# Battery_Charger.net
KiCad netlist of a schematic drawn in Altium Designer
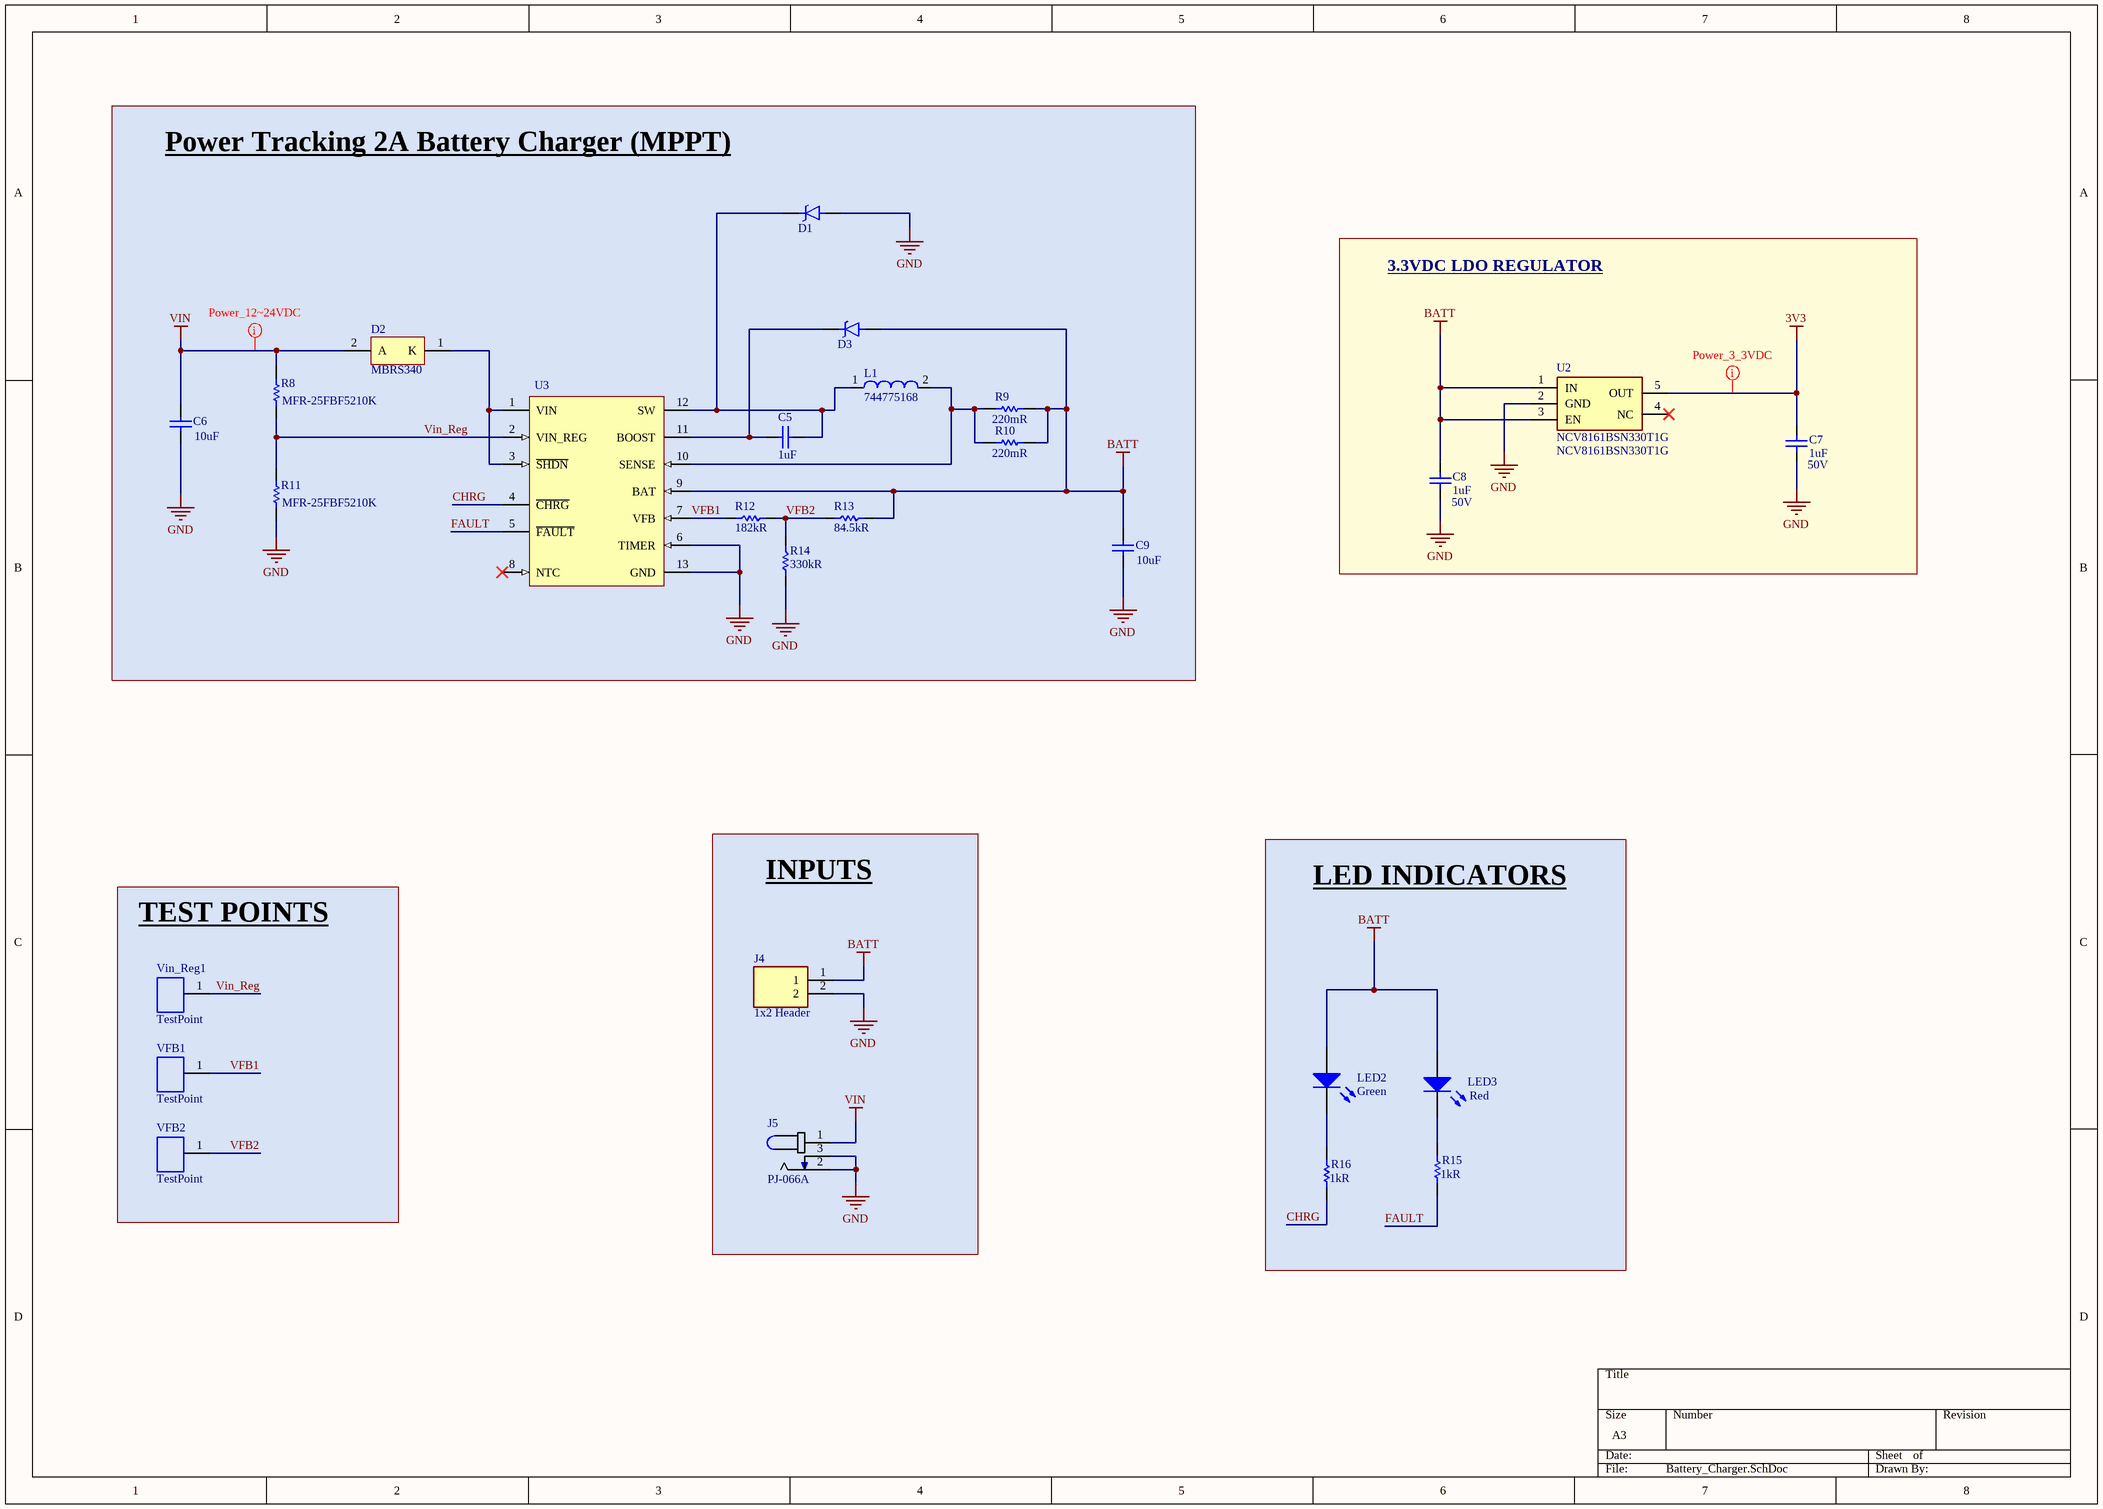
[diagram p0: Battery_Charger.SchDoc]

(export (version "E")
  (design (tool "Eeschema 10.0.6"))
  (components
    (comp (ref "C5")
      (value "https://www.digikey.com/product-detail/en/w-rth-elektronik/885012107015/732-7625-1-ND/5454252")
      (footprint "CAPC0805(2012)100_M")
      (description "CAP CER 1UF 25V X5R 0805")
      (fields
        (field (name "MANUFACTURER") "Wurth Electronics")
        (field (name "MANUFACTURER PART NUMBER") "885012107015")
        (field (name "CAPACITANCE") "1uF")
      )
      (libsource (lib "Altium Content Vault") (part "CAP"))
    )
    (comp (ref "C6")
      (value "https://www.digikey.com/product-detail/en/samsung-electro-mechanics/CL31A106MBHNNNE/1276-6736-1-ND/5961595")
      (footprint "CAPC1206(3216)190_M")
      (description "CAP CER 10UF 50V X5R 1206")
      (fields
        (field (name "MANUFACTURER") "Samsung")
        (field (name "MANUFACTURER PART NUMBER") "CL31A106MBHNNNE")
        (field (name "CAPACITANCE") "10uF")
      )
      (libsource (lib "Altium Content Vault") (part "CAP"))
    )
    (comp (ref "C7")
      (value "1uF")
      (footprint "Cap 0805 (2012 Metric)")
      (description "Cap Ceramic 1uF 50V Y5V -20% to 80% SMD 0805 85C T/R")
      (fields
        (field (name "MANUFACTURER") "Samsung")
        (field (name "MANUFACTURER PART NUMBER") "CL21F105ZBFNNNG")
        (field (name "VOLTAGE RATING") "50V")
      )
      (libsource (lib "Daniel_Integrated_Library") (part "Capacitor"))
    )
    (comp (ref "C8")
      (value "1uF")
      (footprint "Cap 0805 (2012 Metric)")
      (description "Cap Ceramic 1uF 50V Y5V -20% to 80% SMD 0805 85C T/R")
      (fields
        (field (name "MANUFACTURER") "Samsung")
        (field (name "MANUFACTURER PART NUMBER") "CL21F105ZBFNNNG")
        (field (name "VOLTAGE RATING") "50V")
      )
      (libsource (lib "Daniel_Integrated_Library") (part "Capacitor"))
    )
    (comp (ref "C9")
      (value "https://www.digikey.com/product-detail/en/samsung-electro-mechanics/CL31A106MBHNNNE/1276-6736-1-ND/5961595")
      (footprint "CAPC1206(3216)190_M")
      (description "CAP CER 10UF 50V X5R 1206")
      (fields
        (field (name "MANUFACTURER") "Samsung")
        (field (name "MANUFACTURER PART NUMBER") "CL31A106MBHNNNE")
        (field (name "CAPACITANCE") "10uF")
      )
      (libsource (lib "Altium Content Vault") (part "CAP"))
    )
    (comp (ref "D1")
      (value "https://www.digikey.com/product-detail/en/diodes-incorporated/ZLLS500TA/ZLLS500CT-ND/560650")
      (footprint "SOT-23")
      (description "DIODE SCHOTTKY 40V 700MA SOT23-3")
      (fields
        (field (name "MANUFACTURER") "Diodes Zetex")
        (field (name "MANUFACTURER PART NUMBER") "ZLLS500TA")
      )
      (libsource (lib "MyLib") (part "ZLLS500TA"))
    )
    (comp (ref "D2")
      (value "https://www.digikey.com/product-detail/en/on-semiconductor/MBRS340/MBRS340FSCT-ND/965655")
      (footprint "ONSC-SMC-2-403-03_V")
      (description "DIODE SCHOTTKY 40V 4A SMC")
      (fields
        (field (name "MANUFACTURER") "ON Semiconductor / Fairchild")
        (field (name "MANUFACTURER PART NUMBER") "MBRS340")
      )
      (libsource (lib "Altium Content Vault") (part "ONSC-D-K1A2-2_A"))
    )
    (comp (ref "D3")
      (value "https://www.digikey.com/product-detail/en/diodes-incorporated/ZLLS500TA/ZLLS500CT-ND/560650")
      (footprint "SOT-23")
      (description "DIODE SCHOTTKY 40V 700MA SOT23-3")
      (fields
        (field (name "MANUFACTURER") "Diodes Zetex")
        (field (name "MANUFACTURER PART NUMBER") "ZLLS500TA")
      )
      (libsource (lib "MyLib") (part "ZLLS500TA"))
    )
    (comp (ref "J4")
      (value "1x2 Header")
      (footprint "S2B-PH-K-S(LF)(SN)")
      (description "Conn Shrouded Header (4 Sides) HDR 2 POS 2mm Solder RA Thru-Hole Box")
      (fields
        (field (name "MANUFACTURER") "JST")
        (field (name "MANUFACTURER PART NUMBER") "S2B-PH-K-S(LF)(SN)")
      )
      (libsource (lib "Sebas_Integrated_Library") (part "S2B-PH-K-S(LF)(SN)"))
    )
    (comp (ref "J5")
      (value "https://www.digikey.com/product-detail/en/cui-devices/PJ-066A/CP-066A-ND/2627225")
      (footprint "PJ-066A")
      (description "CONN PWR JACK 2X5.5MM SOLDER")
      (fields (field (name "MANUFACTURER") "CUI") (field (name "MANUFACTURER PART NUMBER") "PJ-066A"))
      (libsource (lib "MyLib") (part "PJ-066A"))
    )
    (comp (ref "L1")
      (value "744775168")
      (footprint "WE-PD2-L")
      (description "WE-PD2; Unshielded Wire-wound SMD Inductor with Ferrite Core; 68 µH; 990mA I")
      (fields (field (name "MANUFACTURER") "Wurth Electronics"))
      (libsource (lib "Altium Content Vault") (part "PAS-IND-INDUCTOR-2"))
    )
    (comp (ref "LED2")
      (value "https://www.digikey.com/product-detail/en/osram-opto-semiconductors-inc/LG-R971-KN-1/475-1410-1-ND/1802598")
      (footprint "0805_A")
      (description "LED GREEN DIFFUSED 0805 SMD")
      (fields
        (field (name "PARTNUMBER") "150080GS75000")
        (field (name "MANUFACTURER") "Wuerth Elektronik")
        (field (name "ILLUMINATION COLOR") "Green")
      )
      (libsource (lib "Altium Content Vault") (part "WE-LED_K1A2-2"))
    )
    (comp (ref "LED3")
      (value "https://www.digikey.com/product-detail/en/wurth-electronics-inc/150080RS75000/732-4984-1-ND/4489916")
      (footprint "0805_A")
      (description "LED RED CLEAR 0805 SMD")
      (fields
        (field (name "MANUFACTURER") "Wurth Electronics")
        (field (name "MANUFACTURER PART NUMBER") "150080RS75000")
        (field (name "COLOR") "Red")
      )
      (libsource (lib "Altium Content Vault") (part "WE-LED_K1A2-2"))
    )
    (comp (ref "R8")
      (value "MFR-25FBF5210K")
      (footprint "RESA60-630X240")
      (description "Axial Resistor, 10 KOhm, +/- 1%, 0.25 W, -55 to 155 degC, 2-Pin THD, RoHS, Bulk")
      (fields (field (name "TOLERANCE") "1%") (field (name "MANUFACTURER") "Yageo"))
      (libsource (lib "Altium Content Vault") (part "RES-2"))
    )
    (comp (ref "R9")
      (value "https://www.digikey.com/product-detail/en/panasonic-electronic-components/ERJ-6RQFR22V/P.22DCT-ND/250302")
      (footprint "RESC0805(2012)_N")
      (description "RES 0.22 OHM 1% 1/8W 0805")
      (fields
        (field (name "MANUFACTURER") "Panasonic")
        (field (name "MANUFACTURER PART NUMBER") "ERJ-6RQFR22V")
        (field (name "RESISTANCE") "220mR")
      )
      (libsource (lib "Altium Content Vault") (part "RES"))
    )
    (comp (ref "R10")
      (value "https://www.digikey.com/product-detail/en/panasonic-electronic-components/ERJ-6RQFR22V/P.22DCT-ND/250302")
      (footprint "RESC0805(2012)_N")
      (description "RES 0.22 OHM 1% 1/8W 0805")
      (fields
        (field (name "MANUFACTURER") "Panasonic")
        (field (name "MANUFACTURER PART NUMBER") "ERJ-6RQFR22V")
        (field (name "RESISTANCE") "220mR")
      )
      (libsource (lib "Altium Content Vault") (part "RES"))
    )
    (comp (ref "R11")
      (value "MFR-25FBF5210K")
      (footprint "RESA60-630X240")
      (description "Axial Resistor, 10 KOhm, +/- 1%, 0.25 W, -55 to 155 degC, 2-Pin THD, RoHS, Bulk")
      (fields (field (name "TOLERANCE") "1%") (field (name "MANUFACTURER") "Yageo"))
      (libsource (lib "Altium Content Vault") (part "RES-2"))
    )
    (comp (ref "R12")
      (value "182kR")
      (footprint "Res 0805 (2012 Metric)")
      (description "Res Thick Film 0805 182K Ohm 1% 1/8W ±100ppm/°C Molded SMD Punched Carrier T/R")
      (fields
        (field (name "MANUFACTURER") "Panasonic")
        (field (name "MANUFACTURER PART NUMBER") "ERJ-6ENF1823V")
      )
      (libsource (lib "Daniel_Integrated_Library") (part "Resistor"))
    )
    (comp (ref "R13")
      (value "84.5kR")
      (footprint "Res 0805 (2012 Metric)")
      (description "贴片电阻 84500Ω ± 1.00% 0.125W ± 100ppm/℃ 0805")
      (fields
        (field (name "MANUFACTURER") "Yageo")
        (field (name "MANUFACTURER PART NUMBER") "RC0805FR-0784K5L")
      )
      (libsource (lib "Daniel_Integrated_Library") (part "Resistor"))
    )
    (comp (ref "R14")
      (value "330kR")
      (footprint "Res 0805 (2012 Metric)")
      (description "贴片电阻 330KΩ ±1% 1/8W ±100ppm/℃ 0805")
      (fields
        (field (name "MANUFACTURER") "Panasonic")
        (field (name "MANUFACTURER PART NUMBER") "ERJ6ENF3303V")
      )
      (libsource (lib "Daniel_Integrated_Library") (part "Resistor"))
    )
    (comp (ref "R15")
      (value "https://www.digikey.com/product-detail/en/stackpole-electronics-inc/RNCP0805FTD1K00/RNCP0805FTD1K00CT-ND/2240568")
      (footprint "RESC0805(2012)_M")
      (description "RES 1K OHM 1% 1/4W 0805")
      (fields
        (field (name "MANUFACTURER") "Stackpole Electronics")
        (field (name "MANUFACTURER PART NUMBER") "RNCP0805FTD1K00")
        (field (name "RESISTANCE") "1kR")
      )
      (libsource (lib "Altium Content Vault") (part "RES"))
    )
    (comp (ref "R16")
      (value "https://www.digikey.com/product-detail/en/stackpole-electronics-inc/RNCP0805FTD1K00/RNCP0805FTD1K00CT-ND/2240568")
      (footprint "RESC0805(2012)_M")
      (description "RES 1K OHM 1% 1/4W 0805")
      (fields
        (field (name "MANUFACTURER") "Stackpole Electronics")
        (field (name "MANUFACTURER PART NUMBER") "RNCP0805FTD1K00")
        (field (name "RESISTANCE") "1kR")
      )
      (libsource (lib "Altium Content Vault") (part "RES"))
    )
    (comp (ref "U2")
      (value "NCV8161BSN330T1G")
      (footprint "NCV8161BSN330T1G")
      (description "ON SEMICONDUCTOR - NCV8161BSN330T1G - LDO-FESTSP.REG AEC-Q100 3.3V 0.45A TSOP5")
      (fields
        (field (name "MANUFACTURER") "ON Semiconductor")
        (field (name "MANUFACTURER PART NUMBER") "NCV8161BSN330T1G")
      )
      (libsource (lib "stratos") (part "NCV8161BSN330T1G"))
    )
    (comp (ref "U3")
      (value "https://www.digikey.com/product-detail/en/linear-technology-analog-devices/LT3652HVEMSE-TRPBF/LT3652HVEMSE-TRPBFCT-ND/8040618")
      (footprint "12-Lead Plastic MSOP")
      (description "IC BATTERY CHARGER 2A 12-MSOP")
      (fields
        (field (name "MANUFACTURER") "Analog Devices / Linear Technology")
        (field (name "MANUFACTURER PART NUMBER") "LT3652HVEMSE#TRPBF")
      )
      (libsource (lib "MyLib") (part "LT3652HVEMSE#TRPBF"))
    )
    (comp (ref "VFB1")
      (value "TestPoint")
      (footprint "TestPoint")
      (libsource (lib "MyLib") (part "TestPoint"))
    )
    (comp (ref "VFB2")
      (value "TestPoint")
      (footprint "TestPoint")
      (libsource (lib "MyLib") (part "TestPoint"))
    )
    (comp (ref "Vin_Reg1")
      (value "TestPoint")
      (footprint "TestPoint")
      (libsource (lib "MyLib") (part "TestPoint"))
    )
  )
  (nets
    (net (code "1") (name "/CHRG") (class "Default")
      (node (ref "R16") (pin "2") (pinfunction "2_2") (pintype "passive"))
      (node (ref "U3") (pin "4") (pinfunction "~{CHRG}_4") (pintype "tri_state"))
    )
    (net (code "2") (name "/FAULT") (class "Default")
      (node (ref "R15") (pin "2") (pinfunction "2_2") (pintype "passive"))
      (node (ref "U3") (pin "5") (pinfunction "~{FAULT}_5") (pintype "tri_state"))
    )
    (net (code "3") (name "/VFB1") (class "Default")
      (node (ref "R12") (pin "1") (pinfunction "1_1") (pintype "passive"))
      (node (ref "U3") (pin "7") (pinfunction "VFB_7") (pintype "input"))
      (node (ref "VFB1") (pin "1") (pinfunction "1_1") (pintype "passive"))
    )
    (net (code "4") (name "/VFB2") (class "Default")
      (node (ref "R12") (pin "2") (pinfunction "2_2") (pintype "passive"))
      (node (ref "R13") (pin "1") (pinfunction "1_1") (pintype "passive"))
      (node (ref "R14") (pin "1") (pinfunction "1_1") (pintype "passive"))
      (node (ref "VFB2") (pin "1") (pinfunction "1_1") (pintype "passive"))
    )
    (net (code "5") (name "/Vin_Reg") (class "Default")
      (node (ref "R11") (pin "1") (pinfunction "1_1") (pintype "passive"))
      (node (ref "R8") (pin "2") (pinfunction "2_2") (pintype "passive"))
      (node (ref "U3") (pin "2") (pinfunction "VIN_REG_2") (pintype "input"))
      (node (ref "Vin_Reg1") (pin "1") (pinfunction "1_1") (pintype "passive"))
    )
    (net (code "6") (name "3V3") (class "Default")
      (node (ref "C7") (pin "1") (pinfunction "1_1") (pintype "passive"))
      (node (ref "U2") (pin "5") (pinfunction "OUT_5") (pintype "power_in"))
    )
    (net (code "7") (name "BATT") (class "Default")
      (node (ref "C8") (pin "1") (pinfunction "1_1") (pintype "passive"))
      (node (ref "C9") (pin "2") (pinfunction "2_2") (pintype "passive"))
      (node (ref "D3") (pin "1") (pinfunction "A_1") (pintype "passive"))
      (node (ref "J4") (pin "1") (pinfunction "1_1") (pintype "passive"))
      (node (ref "LED2") (pin "2") (pinfunction "A_2") (pintype "passive"))
      (node (ref "LED3") (pin "2") (pinfunction "A_2") (pintype "passive"))
      (node (ref "R10") (pin "2") (pinfunction "2_2") (pintype "passive"))
      (node (ref "R13") (pin "2") (pinfunction "2_2") (pintype "passive"))
      (node (ref "R9") (pin "2") (pinfunction "2_2") (pintype "passive"))
      (node (ref "U2") (pin "1") (pinfunction "IN_1") (pintype "power_in"))
      (node (ref "U2") (pin "3") (pinfunction "EN_3") (pintype "power_in"))
      (node (ref "U3") (pin "9") (pinfunction "BAT_9") (pintype "input"))
    )
    (net (code "8") (name "GND") (class "Default")
      (node (ref "C6") (pin "1") (pinfunction "1_1") (pintype "passive"))
      (node (ref "C7") (pin "2") (pinfunction "2_2") (pintype "passive"))
      (node (ref "C8") (pin "2") (pinfunction "2_2") (pintype "passive"))
      (node (ref "C9") (pin "1") (pinfunction "1_1") (pintype "passive"))
      (node (ref "D1") (pin "1") (pinfunction "A_1") (pintype "passive"))
      (node (ref "J4") (pin "2") (pinfunction "2_2") (pintype "passive"))
      (node (ref "J5") (pin "2") (pinfunction "2_2") (pintype "passive"))
      (node (ref "J5") (pin "3") (pinfunction "3_3") (pintype "passive"))
      (node (ref "R11") (pin "2") (pinfunction "2_2") (pintype "passive"))
      (node (ref "R14") (pin "2") (pinfunction "2_2") (pintype "passive"))
      (node (ref "U2") (pin "2") (pinfunction "GND_2") (pintype "passive"))
      (node (ref "U3") (pin "13") (pinfunction "GND_13") (pintype "power_in"))
      (node (ref "U3") (pin "6") (pinfunction "TIMER_6") (pintype "input"))
    )
    (net (code "9") (name "Net-(D1-C)") (class "Default")
      (node (ref "C5") (pin "2") (pinfunction "2_2") (pintype "passive"))
      (node (ref "D1") (pin "3") (pinfunction "C_3") (pintype "passive"))
      (node (ref "L1") (pin "1") (pinfunction "1_1") (pintype "passive"))
      (node (ref "U3") (pin "12") (pinfunction "SW_12") (pintype "power_in"))
    )
    (net (code "10") (name "Net-(D2-K)") (class "Default")
      (node (ref "D2") (pin "1") (pinfunction "K_1") (pintype "passive"))
      (node (ref "U3") (pin "1") (pinfunction "VIN_1") (pintype "power_in"))
      (node (ref "U3") (pin "3") (pinfunction "~{SHDN}_3") (pintype "input"))
    )
    (net (code "11") (name "Net-(D3-C)") (class "Default")
      (node (ref "C5") (pin "1") (pinfunction "1_1") (pintype "passive"))
      (node (ref "D3") (pin "3") (pinfunction "C_3") (pintype "passive"))
      (node (ref "U3") (pin "11") (pinfunction "BOOST_11") (pintype "power_in"))
    )
    (net (code "12") (name "Net-(LED2-K)") (class "Default")
      (node (ref "LED2") (pin "1") (pinfunction "K_1") (pintype "passive"))
      (node (ref "R16") (pin "1") (pinfunction "1_1") (pintype "passive"))
    )
    (net (code "13") (name "Net-(LED3-K)") (class "Default")
      (node (ref "LED3") (pin "1") (pinfunction "K_1") (pintype "passive"))
      (node (ref "R15") (pin "1") (pinfunction "1_1") (pintype "passive"))
    )
    (net (code "14") (name "Net-(U3-SENSE)") (class "Default")
      (node (ref "L1") (pin "2") (pinfunction "2_2") (pintype "passive"))
      (node (ref "R10") (pin "1") (pinfunction "1_1") (pintype "passive"))
      (node (ref "R9") (pin "1") (pinfunction "1_1") (pintype "passive"))
      (node (ref "U3") (pin "10") (pinfunction "SENSE_10") (pintype "input"))
    )
    (net (code "15") (name "VIN") (class "Default")
      (node (ref "C6") (pin "2") (pinfunction "2_2") (pintype "passive"))
      (node (ref "D2") (pin "2") (pinfunction "A_2") (pintype "passive"))
      (node (ref "J5") (pin "1") (pinfunction "1_1") (pintype "passive"))
      (node (ref "R8") (pin "1") (pinfunction "1_1") (pintype "passive"))
    )
    (net (code "16") (name "unconnected-(U2-NC-Pad4)") (class "Default")
      (node (ref "U2") (pin "4") (pinfunction "NC_4") (pintype "passive+no_connect"))
    )
    (net (code "17") (name "unconnected-(U3-NTC-Pad8)") (class "Default")
      (node (ref "U3") (pin "8") (pinfunction "NTC_8") (pintype "input+no_connect"))
    )
  )
)
